# ph-sensor.net
KiCad netlist of a schematic drawn in EAGLE
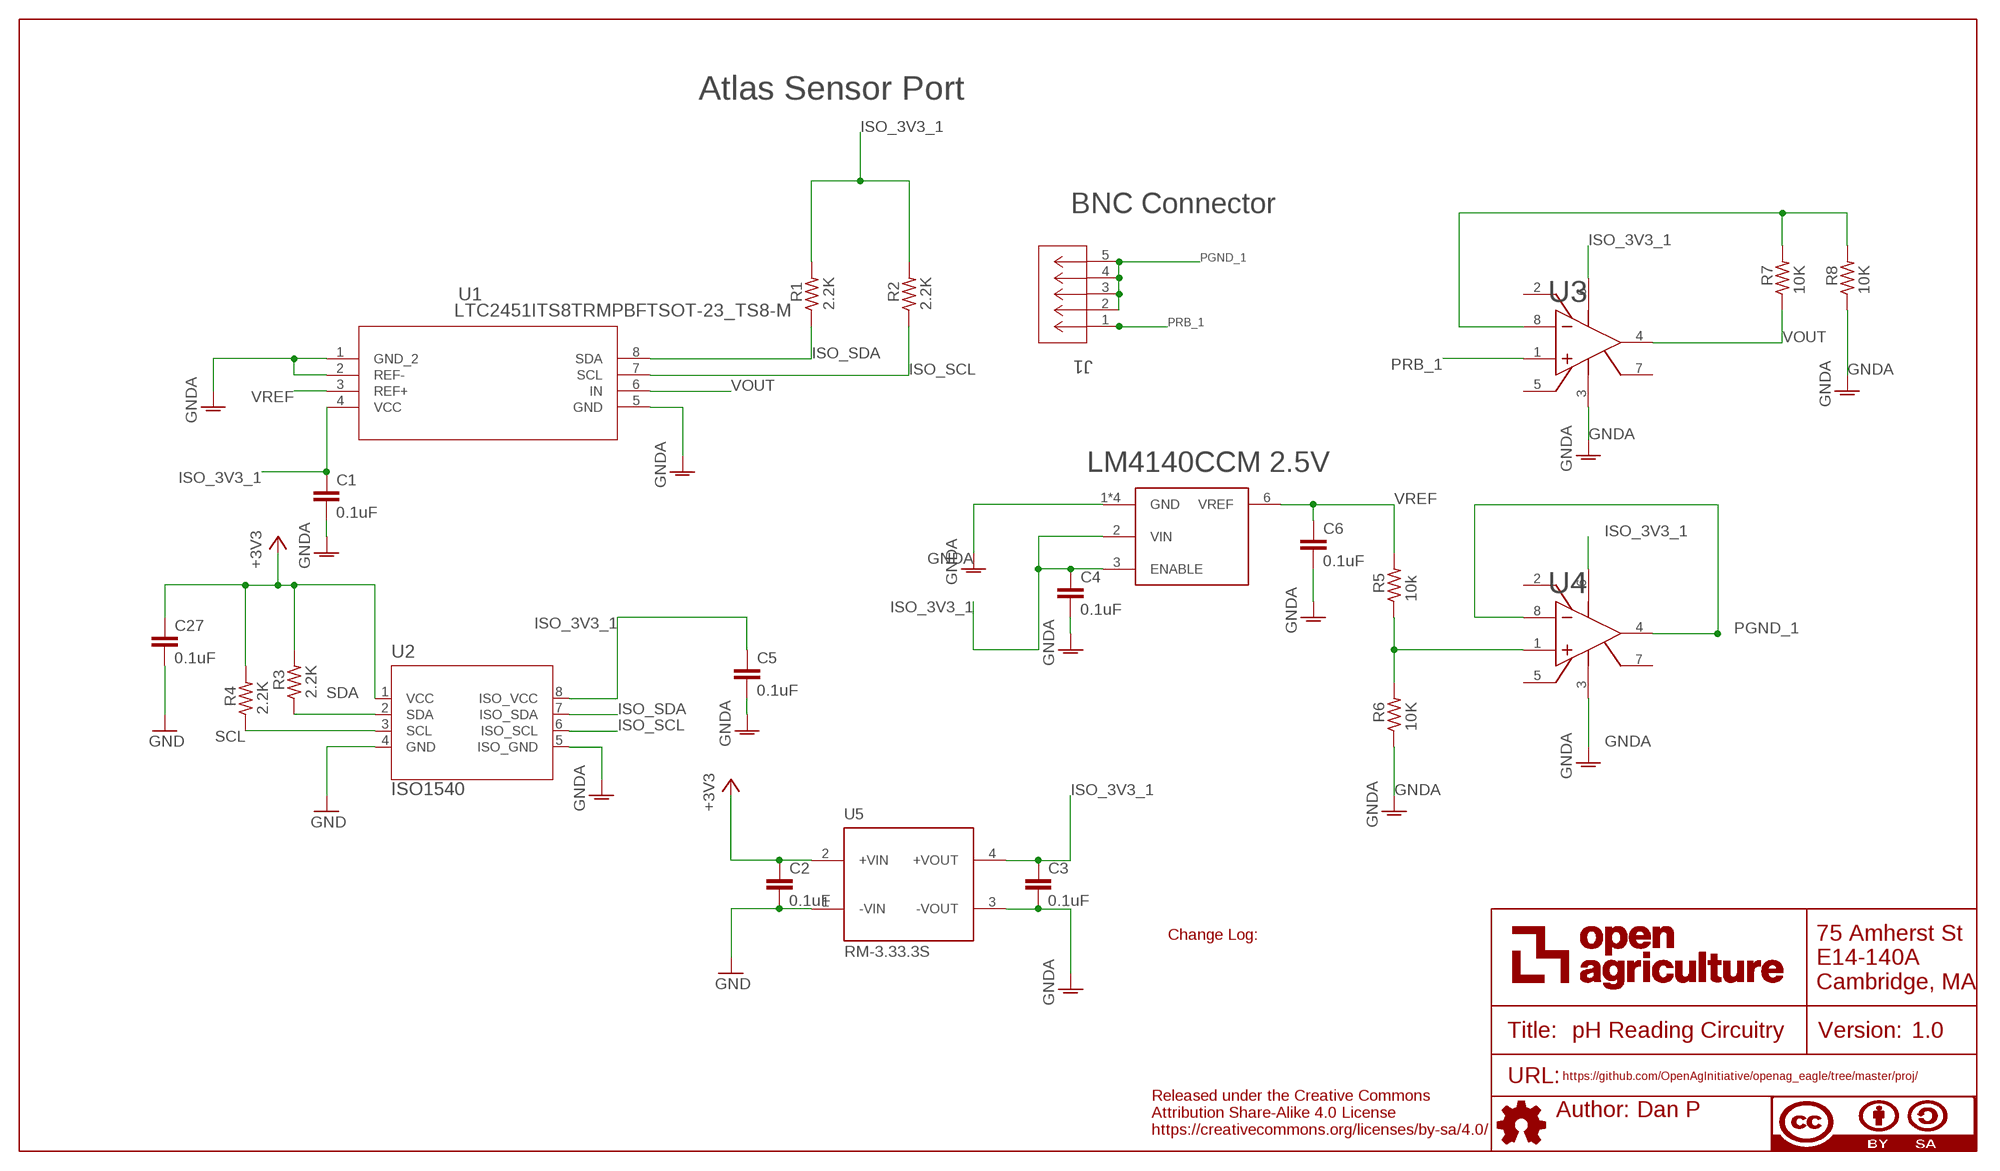
[diagram p0: schematic, sheet 1]

(export (version "E")
  (design (tool "Eeschema 10.0.6"))
  (components
    (comp (ref "C1")
      (value "0.1uF")
      (footprint "eagle-import:C0603")
      (fields (field (name "MANUFACTURER") "Kemet") (field (name "MPN") "C0603C104K5RACTU"))
      (libsource (lib "eagle-import") (part "0.1UF-C0603C104K5RACTU"))
    )
    (comp (ref "C2")
      (value "0.1uF")
      (footprint "eagle-import:C0603")
      (fields (field (name "MANUFACTURER") "Kemet") (field (name "MPN") "C0603C104K5RACTU"))
      (libsource (lib "eagle-import") (part "0.1UF-C0603C104K5RACTU"))
    )
    (comp (ref "C3")
      (value "0.1uF")
      (footprint "eagle-import:C0603")
      (fields (field (name "MANUFACTURER") "Kemet") (field (name "MPN") "C0603C104K5RACTU"))
      (libsource (lib "eagle-import") (part "0.1UF-C0603C104K5RACTU"))
    )
    (comp (ref "C4")
      (value "0.1uF")
      (footprint "eagle-import:C0603")
      (fields (field (name "MANUFACTURER") "Kemet") (field (name "MPN") "C0603C104K5RACTU"))
      (libsource (lib "eagle-import") (part "0.1UF-C0603C104K5RACTU"))
    )
    (comp (ref "C5")
      (value "0.1uF")
      (footprint "eagle-import:C0603")
      (fields (field (name "MANUFACTURER") "Kemet") (field (name "MPN") "C0603C104K5RACTU"))
      (libsource (lib "eagle-import") (part "0.1UF-C0603C104K5RACTU"))
    )
    (comp (ref "C6")
      (value "0.1uF")
      (footprint "eagle-import:C0603")
      (fields (field (name "MANUFACTURER") "Kemet") (field (name "MPN") "C0603C104K5RACTU"))
      (libsource (lib "eagle-import") (part "0.1UF-C0603C104K5RACTU"))
    )
    (comp (ref "C27")
      (value "0.1uF")
      (footprint "eagle-import:C0603")
      (fields (field (name "MANUFACTURER") "Kemet") (field (name "MPN") "C0603C104K5RACTU"))
      (libsource (lib "eagle-import") (part "0.1UF-C0603C104K5RACTU"))
    )
    (comp (ref "J1")
      (value "5-1634503-1")
      (footprint "eagle-import:CONN5_5-1634503-1")
      (fields (field (name "MANUFACTURER_PART_NUMBER") "516345031"))
      (libsource (lib "eagle-import") (part "5-1634503-1"))
    )
    (comp (ref "R1")
      (value "2.2K")
      (footprint "eagle-import:RC0603N")
      (fields (field (name "MANUFACTURER") "Panasonic") (field (name "MPN") "P20283CT-ND"))
      (libsource (lib "eagle-import") (part "1K-ERJ-PB3D1001V"))
    )
    (comp (ref "R2")
      (value "2.2K")
      (footprint "eagle-import:RC0603N")
      (fields (field (name "MANUFACTURER") "Panasonic") (field (name "MPN") "P20283CT-ND"))
      (libsource (lib "eagle-import") (part "1K-ERJ-PB3D1001V"))
    )
    (comp (ref "R3")
      (value "2.2K")
      (footprint "eagle-import:RC0603N")
      (fields (field (name "MANUFACTURER") "Panasonic") (field (name "MPN") "P20283CT-ND"))
      (libsource (lib "eagle-import") (part "1K-ERJ-PB3D1001V"))
    )
    (comp (ref "R4")
      (value "2.2K")
      (footprint "eagle-import:RC0603N")
      (fields (field (name "MANUFACTURER") "Panasonic") (field (name "MPN") "P20283CT-ND"))
      (libsource (lib "eagle-import") (part "1K-ERJ-PB3D1001V"))
    )
    (comp (ref "R5")
      (value "10k")
      (footprint "eagle-import:RC0603N")
      (fields (field (name "MANUFACTURER") "Panasonic") (field (name "MPN") "P20283CT-ND"))
      (libsource (lib "eagle-import") (part "1K-ERJ-PB3D1001V"))
    )
    (comp (ref "R6")
      (value "10K")
      (footprint "eagle-import:RC0603N")
      (fields (field (name "MANUFACTURER") "Panasonic") (field (name "MPN") "P20283CT-ND"))
      (libsource (lib "eagle-import") (part "1K-ERJ-PB3D1001V"))
    )
    (comp (ref "R7")
      (value "10K")
      (footprint "eagle-import:RC0603N")
      (fields (field (name "MANUFACTURER") "Panasonic") (field (name "MPN") "P20283CT-ND"))
      (libsource (lib "eagle-import") (part "1K-ERJ-PB3D1001V"))
    )
    (comp (ref "R8")
      (value "10K")
      (footprint "eagle-import:RC0603N")
      (fields (field (name "MANUFACTURER") "Panasonic") (field (name "MPN") "P20283CT-ND"))
      (libsource (lib "eagle-import") (part "1K-ERJ-PB3D1001V"))
    )
    (comp (ref "U$5")
      (value "LM4140CCM_2.5V")
      (footprint "eagle-import:SO08")
      (libsource (lib "eagle-import") (part "LM4140"))
    )
    (comp (ref "U1")
      (value "LTC2451ITS8TRMPBFTSOT-23_TS8-M")
      (footprint "eagle-import:TSOT-23_TS8-M")
      (fields (field (name "MANUFACTURER_PART_NUMBER") "LTC2451ITS8#TRMPBF"))
      (libsource (lib "eagle-import") (part "LTC2451ITS8TRMPBFTSOT-23_TS8-M"))
    )
    (comp (ref "U2")
      (value "ISO1540")
      (footprint "eagle-import:D8")
      (fields (field (name "MANUFACTURER") "Texas Instruments") (field (name "MPN") "ISO1540DR"))
      (libsource (lib "eagle-import") (part "ISO1540DR"))
    )
    (comp (ref "U3")
      (value "LMP7721MA/NOPBM08A-M")
      (footprint "eagle-import:M08A-M")
      (fields (field (name "MANUFACTURER_PART_NUMBER") "LMP7721MANOPB"))
      (libsource (lib "eagle-import") (part "LMP7721MA/NOPBM08A-M"))
    )
    (comp (ref "U4")
      (value "LMP7721MA/NOPBM08A-M")
      (footprint "eagle-import:M08A-M")
      (fields (field (name "MANUFACTURER_PART_NUMBER") "LMP7721MANOPB"))
      (libsource (lib "eagle-import") (part "LMP7721MA/NOPBM08A-M"))
    )
    (comp (ref "U5")
      (value "RM-3.33.3S")
      (footprint "eagle-import:RM3.33.3S-SIP4")
      (fields (field (name "MANUFACTURER") "Recom Power"))
      (libsource (lib "eagle-import") (part "RM3.33.3S"))
    )
  )
  (nets
    (net (code "1") (name "+3V3") (class "Default")
      (node (ref "C2") (pin "1") (pinfunction "1_1") (pintype "passive"))
      (node (ref "C27") (pin "1") (pinfunction "1_1") (pintype "passive"))
      (node (ref "R3") (pin "2") (pinfunction "2_2") (pintype "passive"))
      (node (ref "R4") (pin "2") (pinfunction "2_2") (pintype "passive"))
      (node (ref "U2") (pin "1") (pinfunction "VCC_1") (pintype "power_in"))
      (node (ref "U5") (pin "2") (pinfunction "+VIN_2") (pintype "power_in"))
    )
    (net (code "2") (name "GND") (class "Default")
      (node (ref "C2") (pin "2") (pinfunction "2_2") (pintype "passive"))
      (node (ref "C27") (pin "2") (pinfunction "2_2") (pintype "passive"))
      (node (ref "U2") (pin "4") (pinfunction "GND_4") (pintype "power_in"))
      (node (ref "U5") (pin "1") (pinfunction "-VIN_1") (pintype "power_in"))
    )
    (net (code "3") (name "GNDA") (class "Default")
      (node (ref "C1") (pin "2") (pinfunction "2_2") (pintype "passive"))
      (node (ref "C3") (pin "2") (pinfunction "2_2") (pintype "passive"))
      (node (ref "C4") (pin "2") (pinfunction "2_2") (pintype "passive"))
      (node (ref "C5") (pin "2") (pinfunction "2_2") (pintype "passive"))
      (node (ref "C6") (pin "2") (pinfunction "2_2") (pintype "passive"))
      (node (ref "R6") (pin "1") (pinfunction "1_1") (pintype "passive"))
      (node (ref "R8") (pin "1") (pinfunction "1_1") (pintype "passive"))
      (node (ref "U$5") (pin "1") (pinfunction "GND_1") (pintype "bidirectional"))
      (node (ref "U$5") (pin "4") (pinfunction "GND_4") (pintype "bidirectional"))
      (node (ref "U$5") (pin "7") (pinfunction "GND_7") (pintype "bidirectional"))
      (node (ref "U$5") (pin "8") (pinfunction "GND_8") (pintype "bidirectional"))
      (node (ref "U1") (pin "1") (pinfunction "GND_2_1") (pintype "power_in"))
      (node (ref "U1") (pin "2") (pinfunction "REF-_2") (pintype "input"))
      (node (ref "U1") (pin "5") (pinfunction "GND_5") (pintype "power_in"))
      (node (ref "U2") (pin "5") (pinfunction "ISO_GND_5") (pintype "power_in"))
      (node (ref "U3") (pin "3") (pinfunction "V-_3") (pintype "power_in"))
      (node (ref "U4") (pin "3") (pinfunction "V-_3") (pintype "power_in"))
      (node (ref "U5") (pin "3") (pinfunction "-VOUT_3") (pintype "power_in"))
    )
    (net (code "4") (name "ISO_3V3_1") (class "Default")
      (node (ref "C1") (pin "1") (pinfunction "1_1") (pintype "passive"))
      (node (ref "C3") (pin "1") (pinfunction "1_1") (pintype "passive"))
      (node (ref "C4") (pin "1") (pinfunction "1_1") (pintype "passive"))
      (node (ref "C5") (pin "1") (pinfunction "1_1") (pintype "passive"))
      (node (ref "R1") (pin "2") (pinfunction "2_2") (pintype "passive"))
      (node (ref "R2") (pin "2") (pinfunction "2_2") (pintype "passive"))
      (node (ref "U$5") (pin "2") (pinfunction "VIN_2") (pintype "bidirectional"))
      (node (ref "U$5") (pin "3") (pinfunction "ENABLE_3") (pintype "bidirectional"))
      (node (ref "U1") (pin "4") (pinfunction "VCC_4") (pintype "power_in"))
      (node (ref "U2") (pin "8") (pinfunction "ISO_VCC_8") (pintype "power_in"))
      (node (ref "U3") (pin "6") (pinfunction "V+_6") (pintype "power_in"))
      (node (ref "U4") (pin "6") (pinfunction "V+_6") (pintype "power_in"))
      (node (ref "U5") (pin "4") (pinfunction "+VOUT_4") (pintype "power_in"))
    )
    (net (code "5") (name "ISO_SCL") (class "Default")
      (node (ref "R2") (pin "1") (pinfunction "1_1") (pintype "passive"))
      (node (ref "U1") (pin "7") (pinfunction "SCL_7") (pintype "input"))
      (node (ref "U2") (pin "6") (pinfunction "ISO_SCL_6") (pintype "bidirectional"))
    )
    (net (code "6") (name "ISO_SDA") (class "Default")
      (node (ref "R1") (pin "1") (pinfunction "1_1") (pintype "passive"))
      (node (ref "U1") (pin "8") (pinfunction "SDA_8") (pintype "bidirectional"))
      (node (ref "U2") (pin "7") (pinfunction "ISO_SDA_7") (pintype "bidirectional"))
    )
    (net (code "7") (name "Net-(U3-IN-)") (class "Default")
      (node (ref "R7") (pin "2") (pinfunction "2_2") (pintype "passive"))
      (node (ref "R8") (pin "2") (pinfunction "2_2") (pintype "passive"))
      (node (ref "U3") (pin "8") (pinfunction "IN-_8") (pintype "input"))
    )
    (net (code "8") (name "Net-(U4-IN+)") (class "Default")
      (node (ref "R5") (pin "1") (pinfunction "1_1") (pintype "passive"))
      (node (ref "R6") (pin "2") (pinfunction "2_2") (pintype "passive"))
      (node (ref "U4") (pin "1") (pinfunction "IN+_1") (pintype "input"))
    )
    (net (code "9") (name "PGND_1") (class "Default")
      (node (ref "J1") (pin "2") (pinfunction "2_2") (pintype "passive"))
      (node (ref "J1") (pin "3") (pinfunction "3_3") (pintype "passive"))
      (node (ref "J1") (pin "4") (pinfunction "4_4") (pintype "passive"))
      (node (ref "J1") (pin "5") (pinfunction "5_5") (pintype "passive"))
      (node (ref "U4") (pin "4") (pinfunction "OUT_4") (pintype "output"))
      (node (ref "U4") (pin "8") (pinfunction "IN-_8") (pintype "input"))
    )
    (net (code "10") (name "PRB_1") (class "Default")
      (node (ref "J1") (pin "1") (pinfunction "1_1") (pintype "passive"))
      (node (ref "U3") (pin "1") (pinfunction "IN+_1") (pintype "input"))
    )
    (net (code "11") (name "SCL") (class "Default")
      (node (ref "R4") (pin "1") (pinfunction "1_1") (pintype "passive"))
      (node (ref "U2") (pin "3") (pinfunction "SCL_3") (pintype "bidirectional"))
    )
    (net (code "12") (name "SDA") (class "Default")
      (node (ref "R3") (pin "1") (pinfunction "1_1") (pintype "passive"))
      (node (ref "U2") (pin "2") (pinfunction "SDA_2") (pintype "bidirectional"))
    )
    (net (code "13") (name "VOUT") (class "Default")
      (node (ref "R7") (pin "1") (pinfunction "1_1") (pintype "passive"))
      (node (ref "U1") (pin "6") (pinfunction "IN_6") (pintype "input"))
      (node (ref "U3") (pin "4") (pinfunction "OUT_4") (pintype "output"))
    )
    (net (code "14") (name "VREF") (class "Default")
      (node (ref "C6") (pin "1") (pinfunction "1_1") (pintype "passive"))
      (node (ref "R5") (pin "2") (pinfunction "2_2") (pintype "passive"))
      (node (ref "U$5") (pin "6") (pinfunction "VREF_6") (pintype "bidirectional"))
      (node (ref "U1") (pin "3") (pinfunction "REF+_3") (pintype "input"))
    )
    (net (code "15") (name "unconnected-(U3-NC-Pad2)") (class "Default")
      (node (ref "U3") (pin "2") (pinfunction "NC_2") (pintype "passive"))
    )
    (net (code "16") (name "unconnected-(U3-NC_2-Pad7)") (class "Default")
      (node (ref "U3") (pin "7") (pinfunction "NC_2_7") (pintype "passive"))
    )
    (net (code "17") (name "unconnected-(U3-NC_3-Pad5)") (class "Default")
      (node (ref "U3") (pin "5") (pinfunction "NC_3_5") (pintype "passive"))
    )
    (net (code "18") (name "unconnected-(U4-NC-Pad2)") (class "Default")
      (node (ref "U4") (pin "2") (pinfunction "NC_2") (pintype "passive"))
    )
    (net (code "19") (name "unconnected-(U4-NC_2-Pad7)") (class "Default")
      (node (ref "U4") (pin "7") (pinfunction "NC_2_7") (pintype "passive"))
    )
    (net (code "20") (name "unconnected-(U4-NC_3-Pad5)") (class "Default")
      (node (ref "U4") (pin "5") (pinfunction "NC_3_5") (pintype "passive"))
    )
  )
)
